# W640J.net
KiCad netlist of a schematic drawn in EAGLE
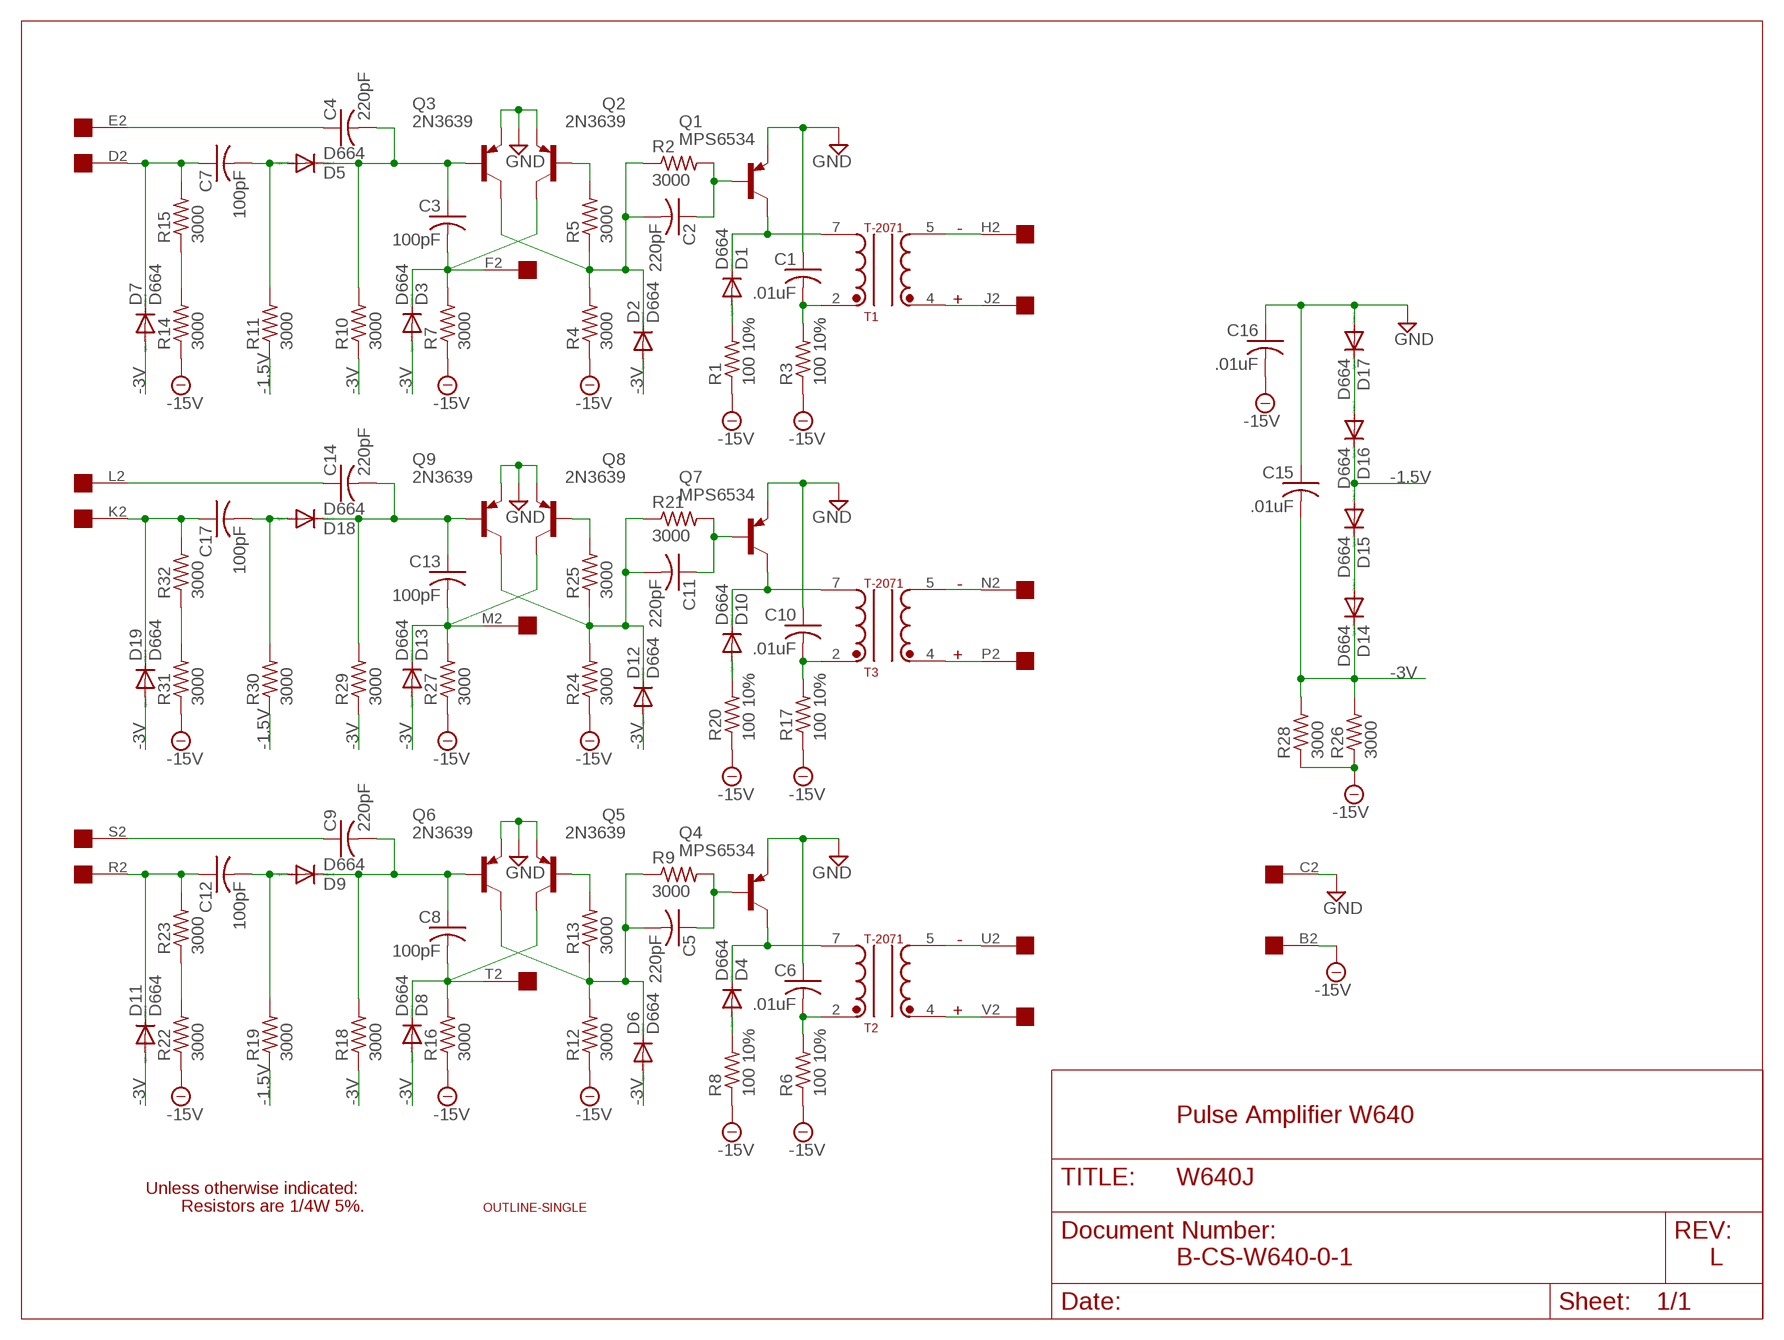
[diagram p0: schematic, sheet 1]

(export (version "E")
  (design (tool "Eeschema 10.0.6"))
  (components
    (comp (ref "C1")
      (value ".01uF")
      (footprint "eagle-import:C063-025X075")
      (libsource (lib "eagle-import") (part "C-US"))
    )
    (comp (ref "C2")
      (value "220pF")
      (footprint "eagle-import:C063-025X075")
      (libsource (lib "eagle-import") (part "C-US"))
    )
    (comp (ref "C3")
      (value "100pF")
      (footprint "eagle-import:C063-025X075")
      (libsource (lib "eagle-import") (part "C-US"))
    )
    (comp (ref "C4")
      (value "220pF")
      (footprint "eagle-import:C063-025X075")
      (libsource (lib "eagle-import") (part "C-US"))
    )
    (comp (ref "C5")
      (value "220pF")
      (footprint "eagle-import:C063-025X075")
      (libsource (lib "eagle-import") (part "C-US"))
    )
    (comp (ref "C6")
      (value ".01uF")
      (footprint "eagle-import:C063-025X075")
      (libsource (lib "eagle-import") (part "C-US"))
    )
    (comp (ref "C7")
      (value "100pF")
      (footprint "eagle-import:C063-025X075")
      (libsource (lib "eagle-import") (part "C-US"))
    )
    (comp (ref "C8")
      (value "100pF")
      (footprint "eagle-import:C063-025X075")
      (libsource (lib "eagle-import") (part "C-US"))
    )
    (comp (ref "C9")
      (value "220pF")
      (footprint "eagle-import:C063-025X075")
      (libsource (lib "eagle-import") (part "C-US"))
    )
    (comp (ref "C10")
      (value ".01uF")
      (footprint "eagle-import:C063-025X075")
      (libsource (lib "eagle-import") (part "C-US"))
    )
    (comp (ref "C11")
      (value "220pF")
      (footprint "eagle-import:C063-025X075")
      (libsource (lib "eagle-import") (part "C-US"))
    )
    (comp (ref "C12")
      (value "100pF")
      (footprint "eagle-import:C063-025X075")
      (libsource (lib "eagle-import") (part "C-US"))
    )
    (comp (ref "C13")
      (value "100pF")
      (footprint "eagle-import:C063-025X075")
      (libsource (lib "eagle-import") (part "C-US"))
    )
    (comp (ref "C14")
      (value "220pF")
      (footprint "eagle-import:C063-025X075")
      (libsource (lib "eagle-import") (part "C-US"))
    )
    (comp (ref "C15")
      (value ".01uF")
      (footprint "eagle-import:C063-025X075")
      (libsource (lib "eagle-import") (part "C-US"))
    )
    (comp (ref "C16")
      (value ".01uF")
      (footprint "eagle-import:C063-025X075")
      (libsource (lib "eagle-import") (part "C-US"))
    )
    (comp (ref "C17")
      (value "100pF")
      (footprint "eagle-import:C063-025X075")
      (libsource (lib "eagle-import") (part "C-US"))
    )
    (comp (ref "D1")
      (value "D664")
      (footprint "eagle-import:DO35-10")
      (libsource (lib "eagle-import") (part "1N4148DO35-10"))
    )
    (comp (ref "D2")
      (value "D664")
      (footprint "eagle-import:DO35-10")
      (libsource (lib "eagle-import") (part "1N4148DO35-10"))
    )
    (comp (ref "D3")
      (value "D664")
      (footprint "eagle-import:DO35-10")
      (libsource (lib "eagle-import") (part "1N4148DO35-10"))
    )
    (comp (ref "D4")
      (value "D664")
      (footprint "eagle-import:DO35-10")
      (libsource (lib "eagle-import") (part "1N4148DO35-10"))
    )
    (comp (ref "D5")
      (value "D664")
      (footprint "eagle-import:DO35-10")
      (libsource (lib "eagle-import") (part "1N4148DO35-10"))
    )
    (comp (ref "D6")
      (value "D664")
      (footprint "eagle-import:DO35-10")
      (libsource (lib "eagle-import") (part "1N4148DO35-10"))
    )
    (comp (ref "D7")
      (value "D664")
      (footprint "eagle-import:DO35-10")
      (libsource (lib "eagle-import") (part "1N4148DO35-10"))
    )
    (comp (ref "D8")
      (value "D664")
      (footprint "eagle-import:DO35-10")
      (libsource (lib "eagle-import") (part "1N4148DO35-10"))
    )
    (comp (ref "D9")
      (value "D664")
      (footprint "eagle-import:DO35-10")
      (libsource (lib "eagle-import") (part "1N4148DO35-10"))
    )
    (comp (ref "D10")
      (value "D664")
      (footprint "eagle-import:DO35-10")
      (libsource (lib "eagle-import") (part "1N4148DO35-10"))
    )
    (comp (ref "D11")
      (value "D664")
      (footprint "eagle-import:DO35-10")
      (libsource (lib "eagle-import") (part "1N4148DO35-10"))
    )
    (comp (ref "D12")
      (value "D664")
      (footprint "eagle-import:DO35-10")
      (libsource (lib "eagle-import") (part "1N4148DO35-10"))
    )
    (comp (ref "D13")
      (value "D664")
      (footprint "eagle-import:DO35-10")
      (libsource (lib "eagle-import") (part "1N4148DO35-10"))
    )
    (comp (ref "D14")
      (value "D664")
      (footprint "eagle-import:DO35-10")
      (libsource (lib "eagle-import") (part "1N4148DO35-10"))
    )
    (comp (ref "D15")
      (value "D664")
      (footprint "eagle-import:DO35-10")
      (libsource (lib "eagle-import") (part "1N4148DO35-10"))
    )
    (comp (ref "D16")
      (value "D664")
      (footprint "eagle-import:DO35-10")
      (libsource (lib "eagle-import") (part "1N4148DO35-10"))
    )
    (comp (ref "D17")
      (value "D664")
      (footprint "eagle-import:DO35-10")
      (libsource (lib "eagle-import") (part "1N4148DO35-10"))
    )
    (comp (ref "D18")
      (value "D664")
      (footprint "eagle-import:DO35-10")
      (libsource (lib "eagle-import") (part "1N4148DO35-10"))
    )
    (comp (ref "D19")
      (value "D664")
      (footprint "eagle-import:DO35-10")
      (libsource (lib "eagle-import") (part "1N4148DO35-10"))
    )
    (comp (ref "Q1")
      (value "MPS6534")
      (footprint "eagle-import:TO5")
      (libsource (lib "eagle-import") (part "-PNP-TO5"))
    )
    (comp (ref "Q2")
      (value "2N3639")
      (footprint "eagle-import:TO5")
      (libsource (lib "eagle-import") (part "-PNP-TO5"))
    )
    (comp (ref "Q3")
      (value "2N3639")
      (footprint "eagle-import:TO5")
      (libsource (lib "eagle-import") (part "-PNP-TO5"))
    )
    (comp (ref "Q4")
      (value "MPS6534")
      (footprint "eagle-import:TO5")
      (libsource (lib "eagle-import") (part "-PNP-TO5"))
    )
    (comp (ref "Q5")
      (value "2N3639")
      (footprint "eagle-import:TO5")
      (libsource (lib "eagle-import") (part "-PNP-TO5"))
    )
    (comp (ref "Q6")
      (value "2N3639")
      (footprint "eagle-import:TO5")
      (libsource (lib "eagle-import") (part "-PNP-TO5"))
    )
    (comp (ref "Q7")
      (value "MPS6534")
      (footprint "eagle-import:TO5")
      (libsource (lib "eagle-import") (part "-PNP-TO5"))
    )
    (comp (ref "Q8")
      (value "2N3639")
      (footprint "eagle-import:TO5")
      (libsource (lib "eagle-import") (part "-PNP-TO5"))
    )
    (comp (ref "Q9")
      (value "2N3639")
      (footprint "eagle-import:TO5")
      (libsource (lib "eagle-import") (part "-PNP-TO5"))
    )
    (comp (ref "R1")
      (value "100 10%")
      (footprint "eagle-import:0207_10")
      (libsource (lib "eagle-import") (part "R-US_0207/10"))
    )
    (comp (ref "R2")
      (value "3000")
      (footprint "eagle-import:0207_10")
      (libsource (lib "eagle-import") (part "R-US_0207/10"))
    )
    (comp (ref "R3")
      (value "100 10%")
      (footprint "eagle-import:0207_10")
      (libsource (lib "eagle-import") (part "R-US_0207/10"))
    )
    (comp (ref "R4")
      (value "3000")
      (footprint "eagle-import:0207_10")
      (libsource (lib "eagle-import") (part "R-US_0207/10"))
    )
    (comp (ref "R5")
      (value "3000")
      (footprint "eagle-import:0207_10")
      (libsource (lib "eagle-import") (part "R-US_0207/10"))
    )
    (comp (ref "R6")
      (value "100 10%")
      (footprint "eagle-import:0207_10")
      (libsource (lib "eagle-import") (part "R-US_0207/10"))
    )
    (comp (ref "R7")
      (value "3000")
      (footprint "eagle-import:0207_10")
      (libsource (lib "eagle-import") (part "R-US_0207/10"))
    )
    (comp (ref "R8")
      (value "100 10%")
      (footprint "eagle-import:0207_10")
      (libsource (lib "eagle-import") (part "R-US_0207/10"))
    )
    (comp (ref "R9")
      (value "3000")
      (footprint "eagle-import:0207_10")
      (libsource (lib "eagle-import") (part "R-US_0207/10"))
    )
    (comp (ref "R10")
      (value "3000")
      (footprint "eagle-import:0207_10")
      (libsource (lib "eagle-import") (part "R-US_0207/10"))
    )
    (comp (ref "R11")
      (value "3000")
      (footprint "eagle-import:0207_10")
      (libsource (lib "eagle-import") (part "R-US_0207/10"))
    )
    (comp (ref "R12")
      (value "3000")
      (footprint "eagle-import:0207_10")
      (libsource (lib "eagle-import") (part "R-US_0207/10"))
    )
    (comp (ref "R13")
      (value "3000")
      (footprint "eagle-import:0207_10")
      (libsource (lib "eagle-import") (part "R-US_0207/10"))
    )
    (comp (ref "R14")
      (value "3000")
      (footprint "eagle-import:0207_10")
      (libsource (lib "eagle-import") (part "R-US_0207/10"))
    )
    (comp (ref "R15")
      (value "3000")
      (footprint "eagle-import:0207_10")
      (libsource (lib "eagle-import") (part "R-US_0207/10"))
    )
    (comp (ref "R16")
      (value "3000")
      (footprint "eagle-import:0207_10")
      (libsource (lib "eagle-import") (part "R-US_0207/10"))
    )
    (comp (ref "R17")
      (value "100 10%")
      (footprint "eagle-import:0207_10")
      (libsource (lib "eagle-import") (part "R-US_0207/10"))
    )
    (comp (ref "R18")
      (value "3000")
      (footprint "eagle-import:0207_10")
      (libsource (lib "eagle-import") (part "R-US_0207/10"))
    )
    (comp (ref "R19")
      (value "3000")
      (footprint "eagle-import:0207_10")
      (libsource (lib "eagle-import") (part "R-US_0207/10"))
    )
    (comp (ref "R20")
      (value "100 10%")
      (footprint "eagle-import:0207_10")
      (libsource (lib "eagle-import") (part "R-US_0207/10"))
    )
    (comp (ref "R21")
      (value "3000")
      (footprint "eagle-import:0207_10")
      (libsource (lib "eagle-import") (part "R-US_0207/10"))
    )
    (comp (ref "R22")
      (value "3000")
      (footprint "eagle-import:0207_10")
      (libsource (lib "eagle-import") (part "R-US_0207/10"))
    )
    (comp (ref "R23")
      (value "3000")
      (footprint "eagle-import:0207_10")
      (libsource (lib "eagle-import") (part "R-US_0207/10"))
    )
    (comp (ref "R24")
      (value "3000")
      (footprint "eagle-import:0207_10")
      (libsource (lib "eagle-import") (part "R-US_0207/10"))
    )
    (comp (ref "R25")
      (value "3000")
      (footprint "eagle-import:0207_10")
      (libsource (lib "eagle-import") (part "R-US_0207/10"))
    )
    (comp (ref "R26")
      (value "3000")
      (footprint "eagle-import:0207_10")
      (libsource (lib "eagle-import") (part "R-US_0207/10"))
    )
    (comp (ref "R27")
      (value "3000")
      (footprint "eagle-import:0207_10")
      (libsource (lib "eagle-import") (part "R-US_0207/10"))
    )
    (comp (ref "R28")
      (value "3000")
      (footprint "eagle-import:0207_10")
      (libsource (lib "eagle-import") (part "R-US_0207/10"))
    )
    (comp (ref "R29")
      (value "3000")
      (footprint "eagle-import:0207_10")
      (libsource (lib "eagle-import") (part "R-US_0207/10"))
    )
    (comp (ref "R30")
      (value "3000")
      (footprint "eagle-import:0207_10")
      (libsource (lib "eagle-import") (part "R-US_0207/10"))
    )
    (comp (ref "R31")
      (value "3000")
      (footprint "eagle-import:0207_10")
      (libsource (lib "eagle-import") (part "R-US_0207/10"))
    )
    (comp (ref "R32")
      (value "3000")
      (footprint "eagle-import:0207_10")
      (libsource (lib "eagle-import") (part "R-US_0207/10"))
    )
    (comp (ref "T1")
      (value "T-2071")
      (footprint "eagle-import:TRANSFORMER")
      (libsource (lib "eagle-import") (part "T-2037"))
    )
    (comp (ref "T2")
      (value "T-2071")
      (footprint "eagle-import:TRANSFORMER")
      (libsource (lib "eagle-import") (part "T-2037"))
    )
    (comp (ref "T3")
      (value "T-2071")
      (footprint "eagle-import:TRANSFORMER")
      (libsource (lib "eagle-import") (part "T-2037"))
    )
    (comp (ref "U$1")
      (value "OUTLINE-SINGLE")
      (footprint "eagle-import:SINGLE")
      (libsource (lib "eagle-import") (part "OUTLINE-SINGLE"))
    )
    (comp (ref "U$2")
      (value "EDGE-1")
      (footprint "eagle-import:EDGE-CON1")
      (libsource (lib "eagle-import") (part "EDGE-1"))
    )
  )
  (nets
    (net (code "1") (name "-15V") (class "Default")
      (node (ref "C16") (pin "2") (pinfunction "2_2") (pintype "passive"))
      (node (ref "R1") (pin "1") (pinfunction "1_1") (pintype "passive"))
      (node (ref "R12") (pin "1") (pinfunction "1_1") (pintype "passive"))
      (node (ref "R14") (pin "1") (pinfunction "1_1") (pintype "passive"))
      (node (ref "R16") (pin "1") (pinfunction "1_1") (pintype "passive"))
      (node (ref "R17") (pin "1") (pinfunction "1_1") (pintype "passive"))
      (node (ref "R20") (pin "1") (pinfunction "1_1") (pintype "passive"))
      (node (ref "R22") (pin "1") (pinfunction "1_1") (pintype "passive"))
      (node (ref "R24") (pin "1") (pinfunction "1_1") (pintype "passive"))
      (node (ref "R26") (pin "1") (pinfunction "1_1") (pintype "passive"))
      (node (ref "R27") (pin "1") (pinfunction "1_1") (pintype "passive"))
      (node (ref "R28") (pin "1") (pinfunction "1_1") (pintype "passive"))
      (node (ref "R3") (pin "1") (pinfunction "1_1") (pintype "passive"))
      (node (ref "R31") (pin "1") (pinfunction "1_1") (pintype "passive"))
      (node (ref "R4") (pin "1") (pinfunction "1_1") (pintype "passive"))
      (node (ref "R6") (pin "1") (pinfunction "1_1") (pintype "passive"))
      (node (ref "R7") (pin "1") (pinfunction "1_1") (pintype "passive"))
      (node (ref "R8") (pin "1") (pinfunction "1_1") (pintype "passive"))
      (node (ref "U$2") (pin "B2") (pinfunction "1_B2") (pintype "bidirectional"))
    )
    (net (code "2") (name "/-1.5V") (class "Default")
      (node (ref "D15") (pin "A") (pinfunction "A_A") (pintype "passive"))
      (node (ref "D16") (pin "C") (pinfunction "C_C") (pintype "passive"))
      (node (ref "R11") (pin "1") (pinfunction "1_1") (pintype "passive"))
      (node (ref "R19") (pin "1") (pinfunction "1_1") (pintype "passive"))
      (node (ref "R30") (pin "1") (pinfunction "1_1") (pintype "passive"))
    )
    (net (code "3") (name "/-3V") (class "Default")
      (node (ref "C15") (pin "2") (pinfunction "2_2") (pintype "passive"))
      (node (ref "D11") (pin "A") (pinfunction "A_A") (pintype "passive"))
      (node (ref "D12") (pin "A") (pinfunction "A_A") (pintype "passive"))
      (node (ref "D13") (pin "A") (pinfunction "A_A") (pintype "passive"))
      (node (ref "D14") (pin "C") (pinfunction "C_C") (pintype "passive"))
      (node (ref "D19") (pin "A") (pinfunction "A_A") (pintype "passive"))
      (node (ref "D2") (pin "A") (pinfunction "A_A") (pintype "passive"))
      (node (ref "D3") (pin "A") (pinfunction "A_A") (pintype "passive"))
      (node (ref "D6") (pin "A") (pinfunction "A_A") (pintype "passive"))
      (node (ref "D7") (pin "A") (pinfunction "A_A") (pintype "passive"))
      (node (ref "D8") (pin "A") (pinfunction "A_A") (pintype "passive"))
      (node (ref "R10") (pin "1") (pinfunction "1_1") (pintype "passive"))
      (node (ref "R18") (pin "1") (pinfunction "1_1") (pintype "passive"))
      (node (ref "R26") (pin "2") (pinfunction "2_2") (pintype "passive"))
      (node (ref "R28") (pin "2") (pinfunction "2_2") (pintype "passive"))
      (node (ref "R29") (pin "1") (pinfunction "1_1") (pintype "passive"))
    )
    (net (code "4") (name "GND") (class "Default")
      (node (ref "C1") (pin "1") (pinfunction "1_1") (pintype "passive"))
      (node (ref "C10") (pin "1") (pinfunction "1_1") (pintype "passive"))
      (node (ref "C15") (pin "1") (pinfunction "1_1") (pintype "passive"))
      (node (ref "C16") (pin "1") (pinfunction "1_1") (pintype "passive"))
      (node (ref "C6") (pin "1") (pinfunction "1_1") (pintype "passive"))
      (node (ref "D17") (pin "A") (pinfunction "A_A") (pintype "passive"))
      (node (ref "Q1") (pin "1") (pinfunction "E_1") (pintype "passive"))
      (node (ref "Q2") (pin "1") (pinfunction "E_1") (pintype "passive"))
      (node (ref "Q3") (pin "1") (pinfunction "E_1") (pintype "passive"))
      (node (ref "Q4") (pin "1") (pinfunction "E_1") (pintype "passive"))
      (node (ref "Q5") (pin "1") (pinfunction "E_1") (pintype "passive"))
      (node (ref "Q6") (pin "1") (pinfunction "E_1") (pintype "passive"))
      (node (ref "Q7") (pin "1") (pinfunction "E_1") (pintype "passive"))
      (node (ref "Q8") (pin "1") (pinfunction "E_1") (pintype "passive"))
      (node (ref "Q9") (pin "1") (pinfunction "E_1") (pintype "passive"))
      (node (ref "U$2") (pin "C2") (pinfunction "1_C2") (pintype "bidirectional"))
    )
    (net (code "5") (name "Net-(C7-Pad2)") (class "Default")
      (node (ref "C7") (pin "2") (pinfunction "2_2") (pintype "passive"))
      (node (ref "D5") (pin "A") (pinfunction "A_A") (pintype "passive"))
      (node (ref "R11") (pin "2") (pinfunction "2_2") (pintype "passive"))
    )
    (net (code "6") (name "Net-(C12-Pad2)") (class "Default")
      (node (ref "C12") (pin "2") (pinfunction "2_2") (pintype "passive"))
      (node (ref "D9") (pin "A") (pinfunction "A_A") (pintype "passive"))
      (node (ref "R19") (pin "2") (pinfunction "2_2") (pintype "passive"))
    )
    (net (code "7") (name "Net-(C17-Pad2)") (class "Default")
      (node (ref "C17") (pin "2") (pinfunction "2_2") (pintype "passive"))
      (node (ref "D18") (pin "A") (pinfunction "A_A") (pintype "passive"))
      (node (ref "R30") (pin "2") (pinfunction "2_2") (pintype "passive"))
    )
    (net (code "8") (name "Net-(D1-PadA)") (class "Default")
      (node (ref "D1") (pin "A") (pinfunction "A_A") (pintype "passive"))
      (node (ref "R1") (pin "2") (pinfunction "2_2") (pintype "passive"))
    )
    (net (code "9") (name "Net-(D4-PadA)") (class "Default")
      (node (ref "D4") (pin "A") (pinfunction "A_A") (pintype "passive"))
      (node (ref "R8") (pin "2") (pinfunction "2_2") (pintype "passive"))
    )
    (net (code "10") (name "Net-(D10-PadA)") (class "Default")
      (node (ref "D10") (pin "A") (pinfunction "A_A") (pintype "passive"))
      (node (ref "R20") (pin "2") (pinfunction "2_2") (pintype "passive"))
    )
    (net (code "11") (name "Net-(D14-PadA)") (class "Default")
      (node (ref "D14") (pin "A") (pinfunction "A_A") (pintype "passive"))
      (node (ref "D15") (pin "C") (pinfunction "C_C") (pintype "passive"))
    )
    (net (code "12") (name "Net-(D16-PadA)") (class "Default")
      (node (ref "D16") (pin "A") (pinfunction "A_A") (pintype "passive"))
      (node (ref "D17") (pin "C") (pinfunction "C_C") (pintype "passive"))
    )
    (net (code "13") (name "Net-(Q1-B)") (class "Default")
      (node (ref "C2") (pin "1") (pinfunction "1_1") (pintype "passive"))
      (node (ref "Q1") (pin "2") (pinfunction "B_2") (pintype "passive"))
      (node (ref "R2") (pin "2") (pinfunction "2_2") (pintype "passive"))
    )
    (net (code "14") (name "Net-(Q1-C)") (class "Default")
      (node (ref "D1") (pin "C") (pinfunction "C_C") (pintype "passive"))
      (node (ref "Q1") (pin "3") (pinfunction "C_3") (pintype "passive"))
      (node (ref "T1") (pin "7") (pinfunction "P$7_7") (pintype "passive"))
    )
    (net (code "15") (name "Net-(Q2-B)") (class "Default")
      (node (ref "Q2") (pin "2") (pinfunction "B_2") (pintype "passive"))
      (node (ref "R5") (pin "2") (pinfunction "2_2") (pintype "passive"))
    )
    (net (code "16") (name "Net-(Q2-C)") (class "Default")
      (node (ref "C3") (pin "2") (pinfunction "2_2") (pintype "passive"))
      (node (ref "D3") (pin "C") (pinfunction "C_C") (pintype "passive"))
      (node (ref "Q2") (pin "3") (pinfunction "C_3") (pintype "passive"))
      (node (ref "R7") (pin "2") (pinfunction "2_2") (pintype "passive"))
      (node (ref "U$2") (pin "F2") (pinfunction "1_F2") (pintype "bidirectional"))
    )
    (net (code "17") (name "Net-(Q3-B)") (class "Default")
      (node (ref "C3") (pin "1") (pinfunction "1_1") (pintype "passive"))
      (node (ref "C4") (pin "2") (pinfunction "2_2") (pintype "passive"))
      (node (ref "D5") (pin "C") (pinfunction "C_C") (pintype "passive"))
      (node (ref "Q3") (pin "2") (pinfunction "B_2") (pintype "passive"))
      (node (ref "R10") (pin "2") (pinfunction "2_2") (pintype "passive"))
    )
    (net (code "18") (name "Net-(Q3-C)") (class "Default")
      (node (ref "C2") (pin "2") (pinfunction "2_2") (pintype "passive"))
      (node (ref "D2") (pin "C") (pinfunction "C_C") (pintype "passive"))
      (node (ref "Q3") (pin "3") (pinfunction "C_3") (pintype "passive"))
      (node (ref "R2") (pin "1") (pinfunction "1_1") (pintype "passive"))
      (node (ref "R4") (pin "2") (pinfunction "2_2") (pintype "passive"))
      (node (ref "R5") (pin "1") (pinfunction "1_1") (pintype "passive"))
    )
    (net (code "19") (name "Net-(Q4-B)") (class "Default")
      (node (ref "C5") (pin "1") (pinfunction "1_1") (pintype "passive"))
      (node (ref "Q4") (pin "2") (pinfunction "B_2") (pintype "passive"))
      (node (ref "R9") (pin "2") (pinfunction "2_2") (pintype "passive"))
    )
    (net (code "20") (name "Net-(Q4-C)") (class "Default")
      (node (ref "D4") (pin "C") (pinfunction "C_C") (pintype "passive"))
      (node (ref "Q4") (pin "3") (pinfunction "C_3") (pintype "passive"))
      (node (ref "T2") (pin "7") (pinfunction "P$7_7") (pintype "passive"))
    )
    (net (code "21") (name "Net-(Q5-B)") (class "Default")
      (node (ref "Q5") (pin "2") (pinfunction "B_2") (pintype "passive"))
      (node (ref "R13") (pin "2") (pinfunction "2_2") (pintype "passive"))
    )
    (net (code "22") (name "Net-(Q5-C)") (class "Default")
      (node (ref "C8") (pin "2") (pinfunction "2_2") (pintype "passive"))
      (node (ref "D8") (pin "C") (pinfunction "C_C") (pintype "passive"))
      (node (ref "Q5") (pin "3") (pinfunction "C_3") (pintype "passive"))
      (node (ref "R16") (pin "2") (pinfunction "2_2") (pintype "passive"))
      (node (ref "U$2") (pin "T2") (pinfunction "1_T2") (pintype "bidirectional"))
    )
    (net (code "23") (name "Net-(Q6-B)") (class "Default")
      (node (ref "C8") (pin "1") (pinfunction "1_1") (pintype "passive"))
      (node (ref "C9") (pin "2") (pinfunction "2_2") (pintype "passive"))
      (node (ref "D9") (pin "C") (pinfunction "C_C") (pintype "passive"))
      (node (ref "Q6") (pin "2") (pinfunction "B_2") (pintype "passive"))
      (node (ref "R18") (pin "2") (pinfunction "2_2") (pintype "passive"))
    )
    (net (code "24") (name "Net-(Q6-C)") (class "Default")
      (node (ref "C5") (pin "2") (pinfunction "2_2") (pintype "passive"))
      (node (ref "D6") (pin "C") (pinfunction "C_C") (pintype "passive"))
      (node (ref "Q6") (pin "3") (pinfunction "C_3") (pintype "passive"))
      (node (ref "R12") (pin "2") (pinfunction "2_2") (pintype "passive"))
      (node (ref "R13") (pin "1") (pinfunction "1_1") (pintype "passive"))
      (node (ref "R9") (pin "1") (pinfunction "1_1") (pintype "passive"))
    )
    (net (code "25") (name "Net-(Q7-B)") (class "Default")
      (node (ref "C11") (pin "1") (pinfunction "1_1") (pintype "passive"))
      (node (ref "Q7") (pin "2") (pinfunction "B_2") (pintype "passive"))
      (node (ref "R21") (pin "2") (pinfunction "2_2") (pintype "passive"))
    )
    (net (code "26") (name "Net-(Q7-C)") (class "Default")
      (node (ref "D10") (pin "C") (pinfunction "C_C") (pintype "passive"))
      (node (ref "Q7") (pin "3") (pinfunction "C_3") (pintype "passive"))
      (node (ref "T3") (pin "7") (pinfunction "P$7_7") (pintype "passive"))
    )
    (net (code "27") (name "Net-(Q8-B)") (class "Default")
      (node (ref "Q8") (pin "2") (pinfunction "B_2") (pintype "passive"))
      (node (ref "R25") (pin "2") (pinfunction "2_2") (pintype "passive"))
    )
    (net (code "28") (name "Net-(Q8-C)") (class "Default")
      (node (ref "C13") (pin "2") (pinfunction "2_2") (pintype "passive"))
      (node (ref "D13") (pin "C") (pinfunction "C_C") (pintype "passive"))
      (node (ref "Q8") (pin "3") (pinfunction "C_3") (pintype "passive"))
      (node (ref "R27") (pin "2") (pinfunction "2_2") (pintype "passive"))
      (node (ref "U$2") (pin "M2") (pinfunction "1_M2") (pintype "bidirectional"))
    )
    (net (code "29") (name "Net-(Q9-B)") (class "Default")
      (node (ref "C13") (pin "1") (pinfunction "1_1") (pintype "passive"))
      (node (ref "C14") (pin "2") (pinfunction "2_2") (pintype "passive"))
      (node (ref "D18") (pin "C") (pinfunction "C_C") (pintype "passive"))
      (node (ref "Q9") (pin "2") (pinfunction "B_2") (pintype "passive"))
      (node (ref "R29") (pin "2") (pinfunction "2_2") (pintype "passive"))
    )
    (net (code "30") (name "Net-(Q9-C)") (class "Default")
      (node (ref "C11") (pin "2") (pinfunction "2_2") (pintype "passive"))
      (node (ref "D12") (pin "C") (pinfunction "C_C") (pintype "passive"))
      (node (ref "Q9") (pin "3") (pinfunction "C_3") (pintype "passive"))
      (node (ref "R21") (pin "1") (pinfunction "1_1") (pintype "passive"))
      (node (ref "R24") (pin "2") (pinfunction "2_2") (pintype "passive"))
      (node (ref "R25") (pin "1") (pinfunction "1_1") (pintype "passive"))
    )
    (net (code "31") (name "Net-(R14-Pad2)") (class "Default")
      (node (ref "R14") (pin "2") (pinfunction "2_2") (pintype "passive"))
      (node (ref "R15") (pin "1") (pinfunction "1_1") (pintype "passive"))
    )
    (net (code "32") (name "Net-(R22-Pad2)") (class "Default")
      (node (ref "R22") (pin "2") (pinfunction "2_2") (pintype "passive"))
      (node (ref "R23") (pin "1") (pinfunction "1_1") (pintype "passive"))
    )
    (net (code "33") (name "Net-(R31-Pad2)") (class "Default")
      (node (ref "R31") (pin "2") (pinfunction "2_2") (pintype "passive"))
      (node (ref "R32") (pin "1") (pinfunction "1_1") (pintype "passive"))
    )
    (net (code "34") (name "Net-(T1-P$2)") (class "Default")
      (node (ref "C1") (pin "2") (pinfunction "2_2") (pintype "passive"))
      (node (ref "R3") (pin "2") (pinfunction "2_2") (pintype "passive"))
      (node (ref "T1") (pin "2") (pinfunction "P$2_2") (pintype "passive"))
    )
    (net (code "35") (name "Net-(T1-P$4)") (class "Default")
      (node (ref "T1") (pin "4") (pinfunction "P$4_4") (pintype "passive"))
      (node (ref "U$2") (pin "J2") (pinfunction "1_J2") (pintype "bidirectional"))
    )
    (net (code "36") (name "Net-(T1-P$5)") (class "Default")
      (node (ref "T1") (pin "5") (pinfunction "P$5_5") (pintype "passive"))
      (node (ref "U$2") (pin "H2") (pinfunction "1_H2") (pintype "bidirectional"))
    )
    (net (code "37") (name "Net-(T2-P$2)") (class "Default")
      (node (ref "C6") (pin "2") (pinfunction "2_2") (pintype "passive"))
      (node (ref "R6") (pin "2") (pinfunction "2_2") (pintype "passive"))
      (node (ref "T2") (pin "2") (pinfunction "P$2_2") (pintype "passive"))
    )
    (net (code "38") (name "Net-(T2-P$4)") (class "Default")
      (node (ref "T2") (pin "4") (pinfunction "P$4_4") (pintype "passive"))
      (node (ref "U$2") (pin "V2") (pinfunction "1_V2") (pintype "bidirectional"))
    )
    (net (code "39") (name "Net-(T2-P$5)") (class "Default")
      (node (ref "T2") (pin "5") (pinfunction "P$5_5") (pintype "passive"))
      (node (ref "U$2") (pin "U2") (pinfunction "1_U2") (pintype "bidirectional"))
    )
    (net (code "40") (name "Net-(T3-P$2)") (class "Default")
      (node (ref "C10") (pin "2") (pinfunction "2_2") (pintype "passive"))
      (node (ref "R17") (pin "2") (pinfunction "2_2") (pintype "passive"))
      (node (ref "T3") (pin "2") (pinfunction "P$2_2") (pintype "passive"))
    )
    (net (code "41") (name "Net-(T3-P$4)") (class "Default")
      (node (ref "T3") (pin "4") (pinfunction "P$4_4") (pintype "passive"))
      (node (ref "U$2") (pin "P2") (pinfunction "1_P2") (pintype "bidirectional"))
    )
    (net (code "42") (name "Net-(T3-P$5)") (class "Default")
      (node (ref "T3") (pin "5") (pinfunction "P$5_5") (pintype "passive"))
      (node (ref "U$2") (pin "N2") (pinfunction "1_N2") (pintype "bidirectional"))
    )
    (net (code "43") (name "Net-(U$2D-1)") (class "Default")
      (node (ref "C7") (pin "1") (pinfunction "1_1") (pintype "passive"))
      (node (ref "D7") (pin "C") (pinfunction "C_C") (pintype "passive"))
      (node (ref "R15") (pin "2") (pinfunction "2_2") (pintype "passive"))
      (node (ref "U$2") (pin "D2") (pinfunction "1_D2") (pintype "bidirectional"))
    )
    (net (code "44") (name "Net-(U$2E-1)") (class "Default")
      (node (ref "C4") (pin "1") (pinfunction "1_1") (pintype "passive"))
      (node (ref "U$2") (pin "E2") (pinfunction "1_E2") (pintype "bidirectional"))
    )
    (net (code "45") (name "Net-(U$2I-1)") (class "Default")
      (node (ref "C17") (pin "1") (pinfunction "1_1") (pintype "passive"))
      (node (ref "D19") (pin "C") (pinfunction "C_C") (pintype "passive"))
      (node (ref "R32") (pin "2") (pinfunction "2_2") (pintype "passive"))
      (node (ref "U$2") (pin "K2") (pinfunction "1_K2") (pintype "bidirectional"))
    )
    (net (code "46") (name "Net-(U$2J-1)") (class "Default")
      (node (ref "C14") (pin "1") (pinfunction "1_1") (pintype "passive"))
      (node (ref "U$2") (pin "L2") (pinfunction "1_L2") (pintype "bidirectional"))
    )
    (net (code "47") (name "Net-(U$2N-1)") (class "Default")
      (node (ref "C12") (pin "1") (pinfunction "1_1") (pintype "passive"))
      (node (ref "D11") (pin "C") (pinfunction "C_C") (pintype "passive"))
      (node (ref "R23") (pin "2") (pinfunction "2_2") (pintype "passive"))
      (node (ref "U$2") (pin "R2") (pinfunction "1_R2") (pintype "bidirectional"))
    )
    (net (code "48") (name "Net-(U$2O-1)") (class "Default")
      (node (ref "C9") (pin "1") (pinfunction "1_1") (pintype "passive"))
      (node (ref "U$2") (pin "S2") (pinfunction "1_S2") (pintype "bidirectional"))
    )
  )
)
